# Dig.net
KiCad netlist of a schematic drawn in EAGLE
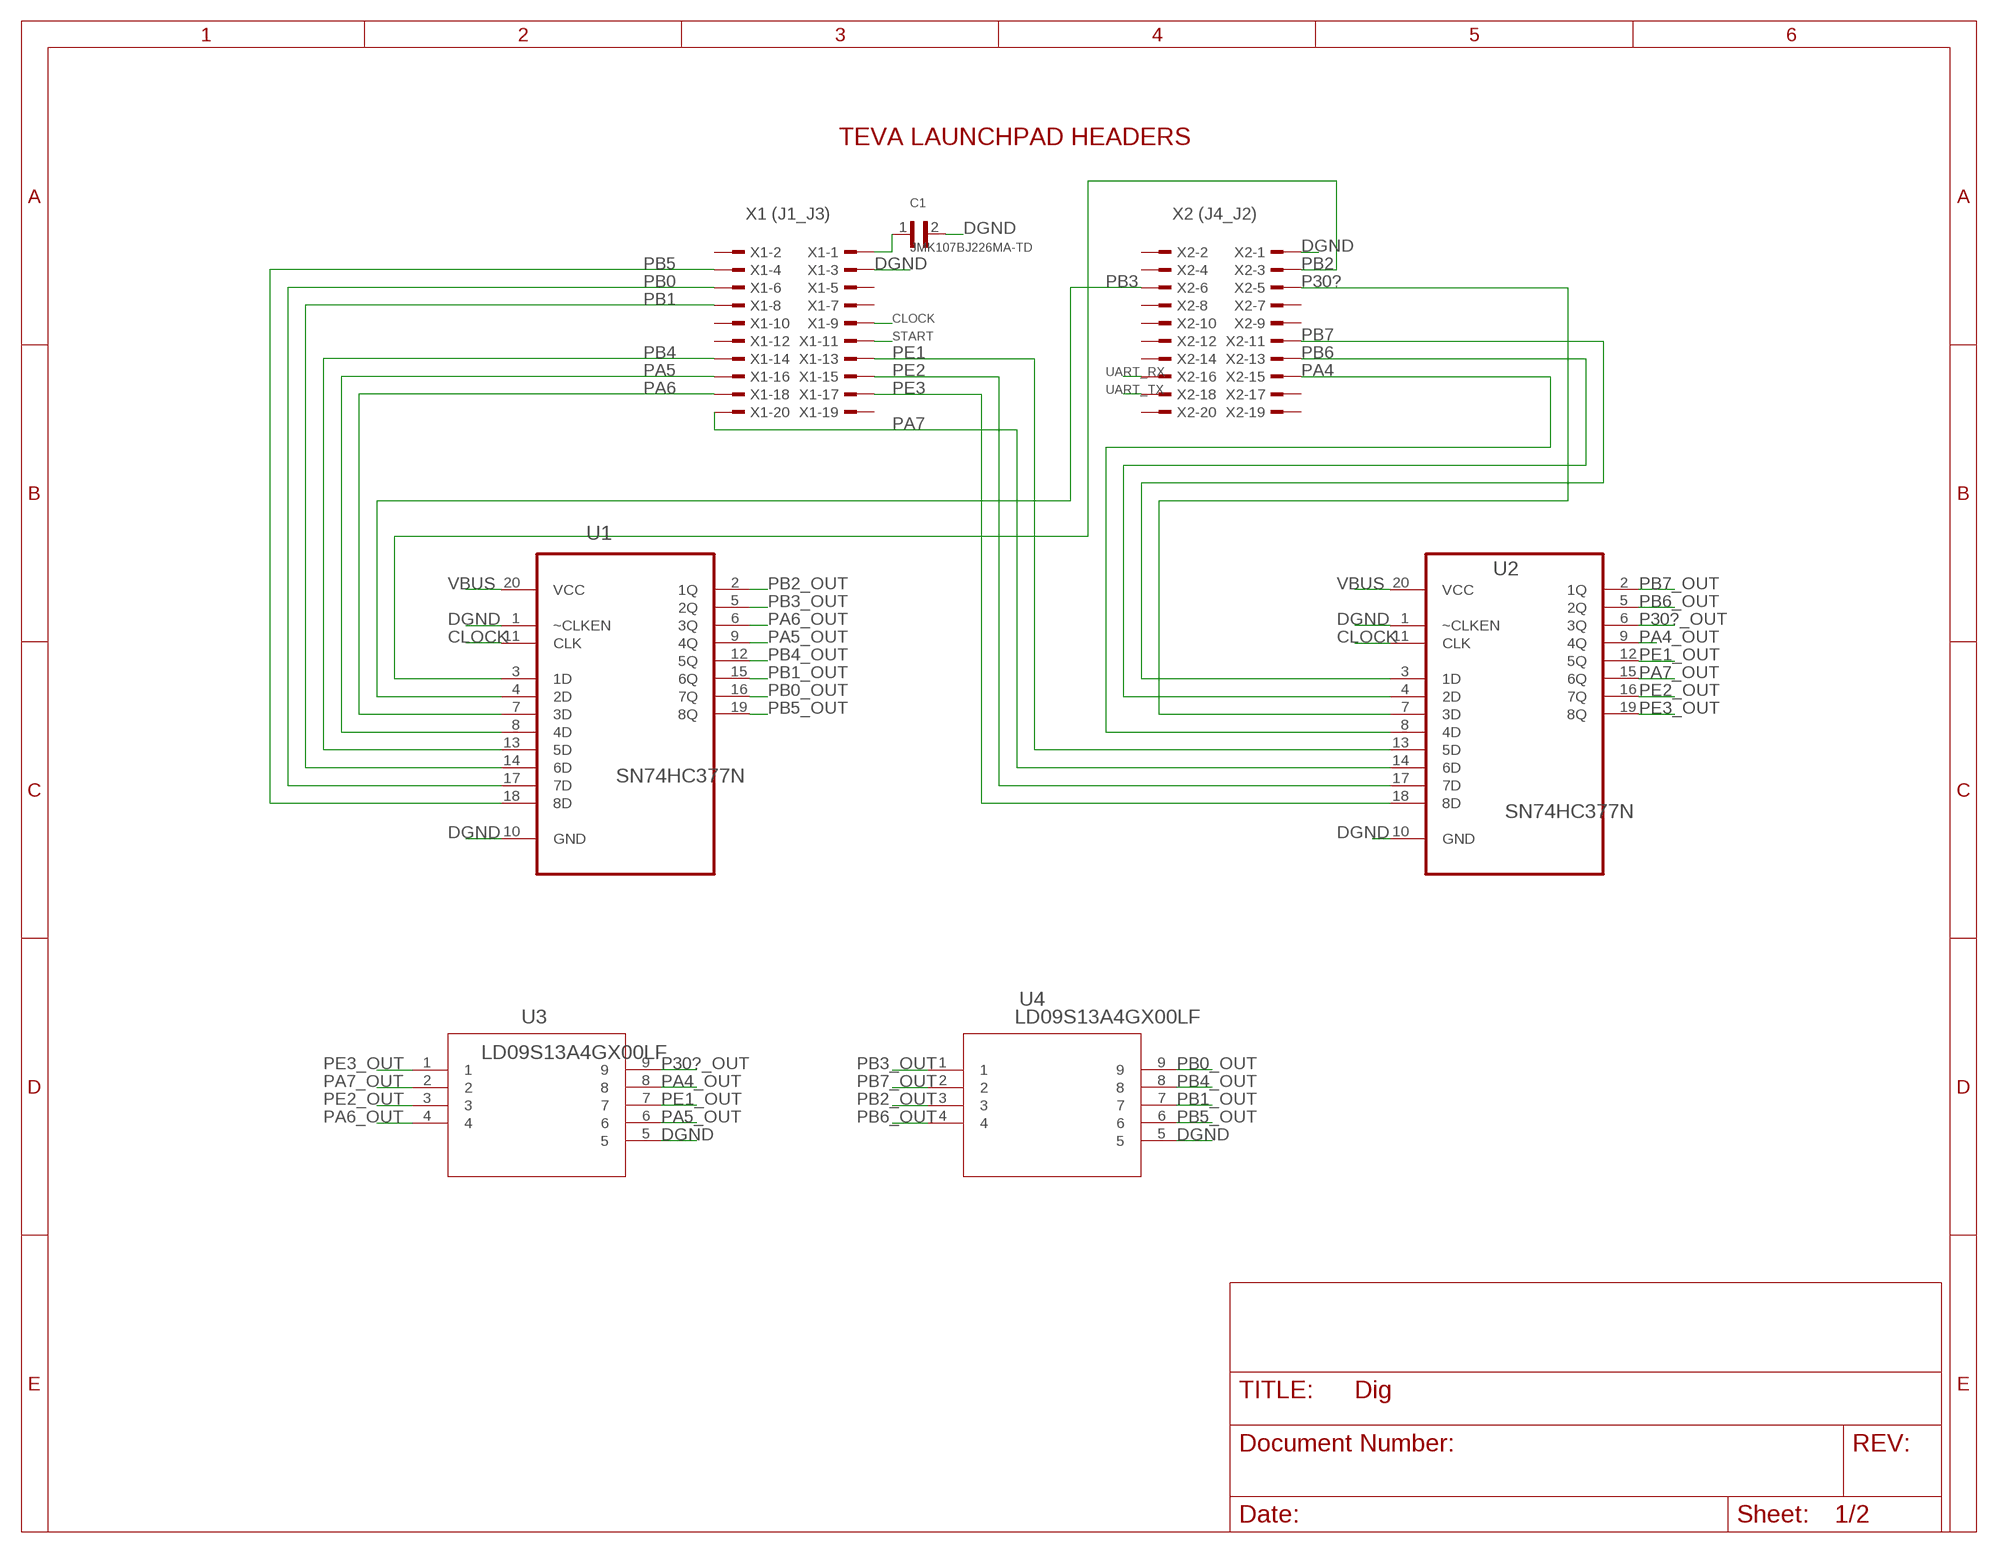
[diagram p0: schematic, sheet 1]
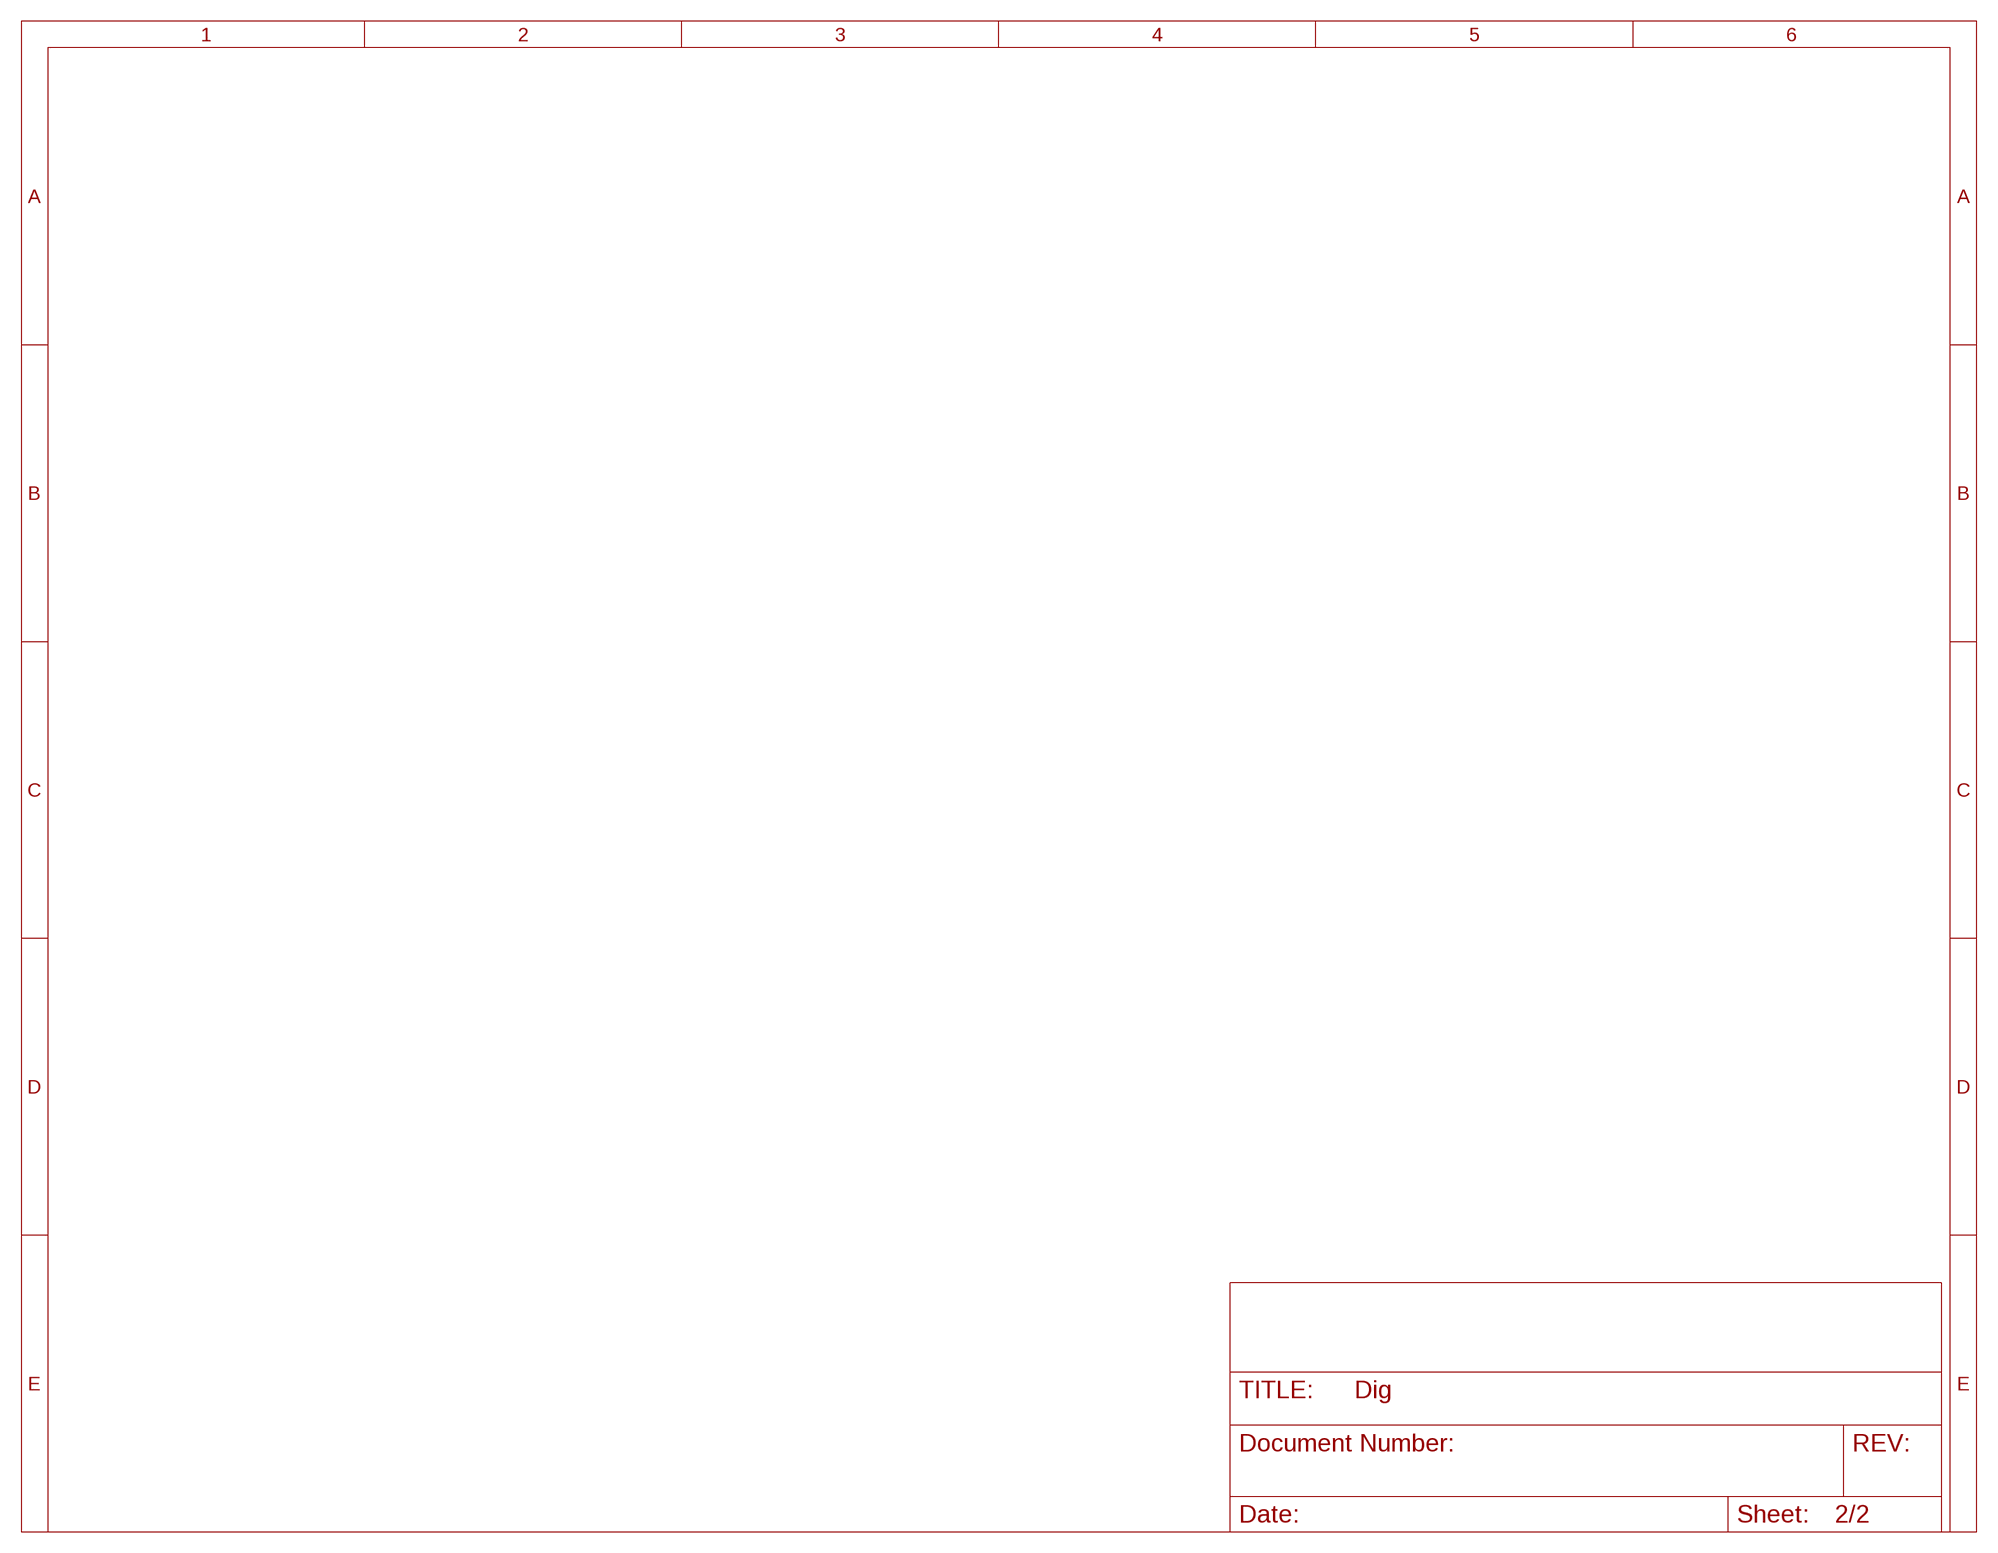
[diagram p1: schematic, sheet 2]

(export (version "E")
  (design (tool "Eeschema 10.0.6"))
  (components
    (comp (ref "C1")
      (value "JMK107BJ226MA-TD")
      (footprint "eagle-import:CAPC1608X90N")
      (fields (field (name "DIGI-KEY_PART_NUMBER") "587-6144-1-ND") (field (name "MF") "Taiyo Yuden"))
      (libsource (lib "eagle-import") (part "JMK107BJ226MA-TD"))
    )
    (comp (ref "U1")
      (value "SN74HC377N")
      (footprint "eagle-import:DIP254P762X508-20")
      (fields (field (name "MF") "Texas Instruments") (field (name "SPICEPREFIX") "U"))
      (libsource (lib "eagle-import") (part "SN74HC377N"))
    )
    (comp (ref "U2")
      (value "SN74HC377N")
      (footprint "eagle-import:DIP254P762X508-20")
      (fields (field (name "MF") "Texas Instruments"))
      (libsource (lib "eagle-import") (part "SN74HC377N"))
    )
    (comp (ref "U3")
      (value "LD09S13A4GX00LF")
      (footprint "eagle-import:LD09S13A4GX00LF_AMP")
      (fields
        (field (name "SPICEPREFIX") "U")
        (field (name "COPYRIGHT") "Copyright (C) 2018 Accelerated Designs. All rights reserved")
      )
      (libsource (lib "eagle-import") (part "LD09S13A4GX00LF"))
    )
    (comp (ref "U4")
      (value "LD09S13A4GX00LF")
      (footprint "eagle-import:LD09S13A4GX00LF_AMP")
      (fields (field (name "COPYRIGHT") "Copyright (C) 2018 Accelerated Designs. All rights reserved"))
      (libsource (lib "eagle-import") (part "LD09S13A4GX00LF"))
    )
    (comp (ref "X1")
      (value "X1 (J1_J3)")
      (footprint "eagle-import:TSW-110-XX-G-D")
      (fields (field (name "MF") "Samtec Inc.") (field (name "MPN") "TSW-110-07-G-D"))
      (libsource (lib "eagle-import") (part "TSW-110--G-D07"))
    )
    (comp (ref "X2")
      (value "X2 (J4_J2)")
      (footprint "eagle-import:TSW-110-XX-G-D")
      (fields (field (name "MF") "Samtec Inc.") (field (name "MPN") "TSW-110-07-G-D"))
      (libsource (lib "eagle-import") (part "TSW-110--G-D07"))
    )
  )
  (nets
    (net (code "1") (name "CLOCK") (class "Default")
      (node (ref "U1") (pin "11") (pinfunction "CLK_11") (pintype "input"))
      (node (ref "U2") (pin "11") (pinfunction "CLK_11") (pintype "input"))
      (node (ref "X1") (pin "9") (pinfunction "1_9") (pintype "passive"))
    )
    (net (code "2") (name "DGND") (class "Default")
      (node (ref "C1") (pin "2") (pinfunction "2_2") (pintype "passive"))
      (node (ref "U1") (pin "1") (pinfunction "~{CLKEN}_1") (pintype "input"))
      (node (ref "U1") (pin "10") (pinfunction "GND_10") (pintype "passive"))
      (node (ref "U2") (pin "1") (pinfunction "~{CLKEN}_1") (pintype "input"))
      (node (ref "U2") (pin "10") (pinfunction "GND_10") (pintype "passive"))
      (node (ref "U3") (pin "5") (pinfunction "5_5") (pintype "passive"))
      (node (ref "U4") (pin "5") (pinfunction "5_5") (pintype "passive"))
      (node (ref "X1") (pin "3") (pinfunction "1_3") (pintype "passive"))
      (node (ref "X2") (pin "1") (pinfunction "1_1") (pintype "passive"))
    )
    (net (code "3") (name "P30?") (class "Default")
      (node (ref "U2") (pin "7") (pinfunction "3D_7") (pintype "input"))
      (node (ref "X2") (pin "5") (pinfunction "1_5") (pintype "passive"))
    )
    (net (code "4") (name "P30?_OUT") (class "Default")
      (node (ref "U2") (pin "6") (pinfunction "3Q_6") (pintype "output"))
      (node (ref "U3") (pin "9") (pinfunction "9_9") (pintype "passive"))
    )
    (net (code "5") (name "PA4") (class "Default")
      (node (ref "U2") (pin "8") (pinfunction "4D_8") (pintype "input"))
      (node (ref "X2") (pin "15") (pinfunction "1_15") (pintype "passive"))
    )
    (net (code "6") (name "PA4_OUT") (class "Default")
      (node (ref "U2") (pin "9") (pinfunction "4Q_9") (pintype "output"))
      (node (ref "U3") (pin "8") (pinfunction "8_8") (pintype "passive"))
    )
    (net (code "7") (name "PA5") (class "Default")
      (node (ref "U1") (pin "8") (pinfunction "4D_8") (pintype "input"))
      (node (ref "X1") (pin "16") (pinfunction "1_16") (pintype "passive"))
    )
    (net (code "8") (name "PA5_OUT") (class "Default")
      (node (ref "U1") (pin "9") (pinfunction "4Q_9") (pintype "output"))
      (node (ref "U3") (pin "6") (pinfunction "6_6") (pintype "passive"))
    )
    (net (code "9") (name "PA6") (class "Default")
      (node (ref "U1") (pin "7") (pinfunction "3D_7") (pintype "input"))
      (node (ref "X1") (pin "18") (pinfunction "1_18") (pintype "passive"))
    )
    (net (code "10") (name "PA6_OUT") (class "Default")
      (node (ref "U1") (pin "6") (pinfunction "3Q_6") (pintype "output"))
      (node (ref "U3") (pin "4") (pinfunction "4_4") (pintype "passive"))
    )
    (net (code "11") (name "PA7") (class "Default")
      (node (ref "U2") (pin "14") (pinfunction "6D_14") (pintype "input"))
      (node (ref "X1") (pin "20") (pinfunction "1_20") (pintype "passive"))
    )
    (net (code "12") (name "PA7_OUT") (class "Default")
      (node (ref "U2") (pin "15") (pinfunction "6Q_15") (pintype "output"))
      (node (ref "U3") (pin "2") (pinfunction "2_2") (pintype "passive"))
    )
    (net (code "13") (name "PB0") (class "Default")
      (node (ref "U1") (pin "17") (pinfunction "7D_17") (pintype "input"))
      (node (ref "X1") (pin "6") (pinfunction "1_6") (pintype "passive"))
    )
    (net (code "14") (name "PB0_OUT") (class "Default")
      (node (ref "U1") (pin "16") (pinfunction "7Q_16") (pintype "output"))
      (node (ref "U4") (pin "9") (pinfunction "9_9") (pintype "passive"))
    )
    (net (code "15") (name "PB1") (class "Default")
      (node (ref "U1") (pin "14") (pinfunction "6D_14") (pintype "input"))
      (node (ref "X1") (pin "8") (pinfunction "1_8") (pintype "passive"))
    )
    (net (code "16") (name "PB1_OUT") (class "Default")
      (node (ref "U1") (pin "15") (pinfunction "6Q_15") (pintype "output"))
      (node (ref "U4") (pin "7") (pinfunction "7_7") (pintype "passive"))
    )
    (net (code "17") (name "PB2") (class "Default")
      (node (ref "U1") (pin "3") (pinfunction "1D_3") (pintype "input"))
      (node (ref "X2") (pin "3") (pinfunction "1_3") (pintype "passive"))
    )
    (net (code "18") (name "PB2_OUT") (class "Default")
      (node (ref "U1") (pin "2") (pinfunction "1Q_2") (pintype "output"))
      (node (ref "U4") (pin "3") (pinfunction "3_3") (pintype "passive"))
    )
    (net (code "19") (name "PB3") (class "Default")
      (node (ref "U1") (pin "4") (pinfunction "2D_4") (pintype "input"))
      (node (ref "X2") (pin "6") (pinfunction "1_6") (pintype "passive"))
    )
    (net (code "20") (name "PB3_OUT") (class "Default")
      (node (ref "U1") (pin "5") (pinfunction "2Q_5") (pintype "output"))
      (node (ref "U4") (pin "1") (pinfunction "1_1") (pintype "passive"))
    )
    (net (code "21") (name "PB4") (class "Default")
      (node (ref "U1") (pin "13") (pinfunction "5D_13") (pintype "input"))
      (node (ref "X1") (pin "14") (pinfunction "1_14") (pintype "passive"))
    )
    (net (code "22") (name "PB4_OUT") (class "Default")
      (node (ref "U1") (pin "12") (pinfunction "5Q_12") (pintype "output"))
      (node (ref "U4") (pin "8") (pinfunction "8_8") (pintype "passive"))
    )
    (net (code "23") (name "PB5") (class "Default")
      (node (ref "U1") (pin "18") (pinfunction "8D_18") (pintype "input"))
      (node (ref "X1") (pin "4") (pinfunction "1_4") (pintype "passive"))
    )
    (net (code "24") (name "PB5_OUT") (class "Default")
      (node (ref "U1") (pin "19") (pinfunction "8Q_19") (pintype "output"))
      (node (ref "U4") (pin "6") (pinfunction "6_6") (pintype "passive"))
    )
    (net (code "25") (name "PB6") (class "Default")
      (node (ref "U2") (pin "4") (pinfunction "2D_4") (pintype "input"))
      (node (ref "X2") (pin "13") (pinfunction "1_13") (pintype "passive"))
    )
    (net (code "26") (name "PB6_OUT") (class "Default")
      (node (ref "U2") (pin "5") (pinfunction "2Q_5") (pintype "output"))
      (node (ref "U4") (pin "4") (pinfunction "4_4") (pintype "passive"))
    )
    (net (code "27") (name "PB7") (class "Default")
      (node (ref "U2") (pin "3") (pinfunction "1D_3") (pintype "input"))
      (node (ref "X2") (pin "11") (pinfunction "1_11") (pintype "passive"))
    )
    (net (code "28") (name "PB7_OUT") (class "Default")
      (node (ref "U2") (pin "2") (pinfunction "1Q_2") (pintype "output"))
      (node (ref "U4") (pin "2") (pinfunction "2_2") (pintype "passive"))
    )
    (net (code "29") (name "PE1") (class "Default")
      (node (ref "U2") (pin "13") (pinfunction "5D_13") (pintype "input"))
      (node (ref "X1") (pin "13") (pinfunction "1_13") (pintype "passive"))
    )
    (net (code "30") (name "PE1_OUT") (class "Default")
      (node (ref "U2") (pin "12") (pinfunction "5Q_12") (pintype "output"))
      (node (ref "U3") (pin "7") (pinfunction "7_7") (pintype "passive"))
    )
    (net (code "31") (name "PE2") (class "Default")
      (node (ref "U2") (pin "17") (pinfunction "7D_17") (pintype "input"))
      (node (ref "X1") (pin "15") (pinfunction "1_15") (pintype "passive"))
    )
    (net (code "32") (name "PE2_OUT") (class "Default")
      (node (ref "U2") (pin "16") (pinfunction "7Q_16") (pintype "output"))
      (node (ref "U3") (pin "3") (pinfunction "3_3") (pintype "passive"))
    )
    (net (code "33") (name "PE3") (class "Default")
      (node (ref "U2") (pin "18") (pinfunction "8D_18") (pintype "input"))
      (node (ref "X1") (pin "17") (pinfunction "1_17") (pintype "passive"))
    )
    (net (code "34") (name "PE3_OUT") (class "Default")
      (node (ref "U2") (pin "19") (pinfunction "8Q_19") (pintype "output"))
      (node (ref "U3") (pin "1") (pinfunction "1_1") (pintype "passive"))
    )
    (net (code "35") (name "START") (class "Default")
      (node (ref "X1") (pin "11") (pinfunction "1_11") (pintype "passive"))
    )
    (net (code "36") (name "UART_RX") (class "Default")
      (node (ref "X2") (pin "16") (pinfunction "1_16") (pintype "passive"))
    )
    (net (code "37") (name "UART_TX") (class "Default")
      (node (ref "X2") (pin "18") (pinfunction "1_18") (pintype "passive"))
    )
    (net (code "38") (name "VBUS") (class "Default")
      (node (ref "C1") (pin "1") (pinfunction "1_1") (pintype "passive"))
      (node (ref "U1") (pin "20") (pinfunction "VCC_20") (pintype "power_in"))
      (node (ref "U2") (pin "20") (pinfunction "VCC_20") (pintype "power_in"))
      (node (ref "X1") (pin "1") (pinfunction "1_1") (pintype "passive"))
    )
    (net (code "39") (name "unconnected-(X1B-1-Pad10)") (class "Default")
      (node (ref "X1") (pin "10") (pinfunction "1_10") (pintype "passive"))
    )
    (net (code "40") (name "unconnected-(X1D-1-Pad12)") (class "Default")
      (node (ref "X1") (pin "12") (pinfunction "1_12") (pintype "passive"))
    )
    (net (code "41") (name "unconnected-(X1K-1-Pad19)") (class "Default")
      (node (ref "X1") (pin "19") (pinfunction "1_19") (pintype "passive"))
    )
    (net (code "42") (name "unconnected-(X1L-1-Pad2)") (class "Default")
      (node (ref "X1") (pin "2") (pinfunction "1_2") (pintype "passive"))
    )
    (net (code "43") (name "unconnected-(X1P-1-Pad5)") (class "Default")
      (node (ref "X1") (pin "5") (pinfunction "1_5") (pintype "passive"))
    )
    (net (code "44") (name "unconnected-(X1R-1-Pad7)") (class "Default")
      (node (ref "X1") (pin "7") (pinfunction "1_7") (pintype "passive"))
    )
    (net (code "45") (name "unconnected-(X2B-1-Pad10)") (class "Default")
      (node (ref "X2") (pin "10") (pinfunction "1_10") (pintype "passive"))
    )
    (net (code "46") (name "unconnected-(X2D-1-Pad12)") (class "Default")
      (node (ref "X2") (pin "12") (pinfunction "1_12") (pintype "passive"))
    )
    (net (code "47") (name "unconnected-(X2F-1-Pad14)") (class "Default")
      (node (ref "X2") (pin "14") (pinfunction "1_14") (pintype "passive"))
    )
    (net (code "48") (name "unconnected-(X2I-1-Pad17)") (class "Default")
      (node (ref "X2") (pin "17") (pinfunction "1_17") (pintype "passive"))
    )
    (net (code "49") (name "unconnected-(X2K-1-Pad19)") (class "Default")
      (node (ref "X2") (pin "19") (pinfunction "1_19") (pintype "passive"))
    )
    (net (code "50") (name "unconnected-(X2L-1-Pad2)") (class "Default")
      (node (ref "X2") (pin "2") (pinfunction "1_2") (pintype "passive"))
    )
    (net (code "51") (name "unconnected-(X2M-1-Pad20)") (class "Default")
      (node (ref "X2") (pin "20") (pinfunction "1_20") (pintype "passive"))
    )
    (net (code "52") (name "unconnected-(X2O-1-Pad4)") (class "Default")
      (node (ref "X2") (pin "4") (pinfunction "1_4") (pintype "passive"))
    )
    (net (code "53") (name "unconnected-(X2R-1-Pad7)") (class "Default")
      (node (ref "X2") (pin "7") (pinfunction "1_7") (pintype "passive"))
    )
    (net (code "54") (name "unconnected-(X2S-1-Pad8)") (class "Default")
      (node (ref "X2") (pin "8") (pinfunction "1_8") (pintype "passive"))
    )
    (net (code "55") (name "unconnected-(X2T-1-Pad9)") (class "Default")
      (node (ref "X2") (pin "9") (pinfunction "1_9") (pintype "passive"))
    )
  )
)
